# Sheet4.net
KiCad netlist of a schematic drawn in Altium Designer
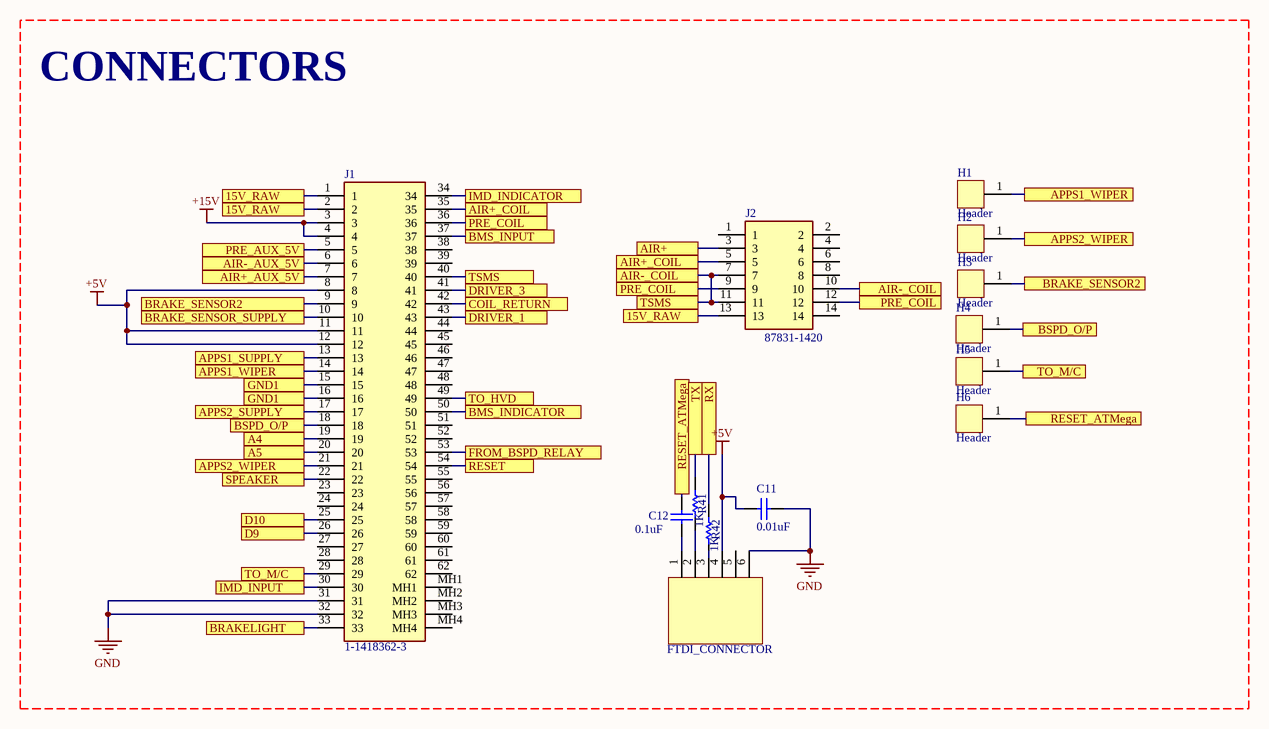
[diagram p0: Sheet4.SchDoc]

(export (version "E")
  (design (tool "Eeschema 10.0.6"))
  (components
    (comp (ref "2")
      (value "FTDI_connector")
      (footprint "FTDI")
      (libsource (lib "Schlib1") (part "FTDI_connector"))
    )
    (comp (ref "C11")
      (value "0.01uF")
      (footprint "KEMT-1206-2_N")
      (description "CAP, Ceramic, 0.1 uF, +/- 10%, 50 V, -55 to 125 degC, 1206 (3216 Metric), RoHS, Tape and Reel")
      (fields (field (name "MANUFACTURER") "Kemet"))
      (libsource (lib "Schlib1_TSAL_LV_3.1") (part "CMP-1037-04202-2"))
    )
    (comp (ref "C12")
      (value "0.1uF")
      (footprint "KEMT-1206-2_N")
      (description "CAP, Ceramic, 0.1 uF, +/- 10%, 50 V, -55 to 125 degC, 1206 (3216 Metric), RoHS, Tape and Reel")
      (fields (field (name "MANUFACTURER") "Kemet"))
      (libsource (lib "Schlib1_TSAL_LV_3.1") (part "CMP-1037-04202-2"))
    )
    (comp (ref "H1") (value "Header") (footprint "Header") (libsource (lib "Schlib1") (part "Header")))
    (comp (ref "H2") (value "Header") (footprint "Header") (libsource (lib "Schlib1") (part "Header")))
    (comp (ref "H3") (value "Header") (footprint "Header") (libsource (lib "Schlib1") (part "Header")))
    (comp (ref "H4") (value "Header") (footprint "Header") (libsource (lib "Schlib1") (part "Header")))
    (comp (ref "H5") (value "Header") (footprint "Header") (libsource (lib "Schlib1") (part "Header")))
    (comp (ref "H6") (value "Header") (footprint "Header") (libsource (lib "Schlib1") (part "Header")))
    (comp (ref "J1")
      (value "1-1418362-3")
      (footprint "SamacSys:114183623")
      (description "Connector")
      (fields (field (name "MOUSER PART NUMBER") "571-1-1418362-3"))
      (libsource (lib "*") (part "1-1418362-3"))
    )
    (comp (ref "J2")
      (value "87831-1420")
      (footprint "SamacSys:SHDR14W55P200_2X7_1665X630X640P")
      (description "Connector")
      (fields (field (name "MOUSER PART NUMBER") "538-87831-1420"))
      (libsource (lib "*") (part "87831-1420"))
    )
    (comp (ref "R41")
      (value "1K")
      (footprint "R1206")
      (fields (field (name "PART NUMBER") "CRCW120647K0FKEA") (field (name "MANUFACTURER") "Vishay Dale"))
      (libsource (lib "Schlib1") (part "RES"))
    )
    (comp (ref "R42")
      (value "1K")
      (footprint "R1206")
      (fields (field (name "PART NUMBER") "CRCW120647K0FKEA") (field (name "MANUFACTURER") "Vishay Dale"))
      (libsource (lib "Schlib1") (part "RES"))
    )
  )
  (nets
    (net (code "1") (name "+5V") (class "Default")
      (node (ref "2") (pin "4") (pinfunction "4_4") (pintype "passive"))
      (node (ref "C11") (pin "2") (pinfunction "2_2") (pintype "passive"))
      (node (ref "J1") (pin "11") (pinfunction "11_11") (pintype "passive"))
      (node (ref "J1") (pin "12") (pinfunction "12_12") (pintype "passive"))
      (node (ref "J1") (pin "8") (pinfunction "8_8") (pintype "passive"))
    )
    (net (code "2") (name "+15V") (class "Default")
      (node (ref "J1") (pin "3") (pinfunction "3_3") (pintype "passive"))
      (node (ref "J1") (pin "4") (pinfunction "4_4") (pintype "passive"))
    )
    (net (code "3") (name "/15V_RAW") (class "Default")
      (node (ref "J1") (pin "1") (pinfunction "1_1") (pintype "passive"))
      (node (ref "J1") (pin "2") (pinfunction "2_2") (pintype "passive"))
      (node (ref "J2") (pin "13") (pinfunction "13_13") (pintype "passive"))
    )
    (net (code "4") (name "/A4") (class "Default")
      (node (ref "J1") (pin "19") (pinfunction "19_19") (pintype "passive"))
    )
    (net (code "5") (name "/A5") (class "Default")
      (node (ref "J1") (pin "20") (pinfunction "20_20") (pintype "passive"))
    )
    (net (code "6") (name "/AIR+") (class "Default")
      (node (ref "J2") (pin "3") (pinfunction "3_3") (pintype "passive"))
    )
    (net (code "7") (name "/AIR+_AUX_5V") (class "Default")
      (node (ref "J1") (pin "7") (pinfunction "7_7") (pintype "passive"))
    )
    (net (code "8") (name "/AIR+_COIL") (class "Default")
      (node (ref "J1") (pin "35") (pinfunction "35_35") (pintype "passive"))
      (node (ref "J2") (pin "5") (pinfunction "5_5") (pintype "passive"))
    )
    (net (code "9") (name "/AIR-_AUX_5V") (class "Default")
      (node (ref "J1") (pin "6") (pinfunction "6_6") (pintype "passive"))
    )
    (net (code "10") (name "/AIR-_COIL") (class "Default")
      (node (ref "J1") (pin "40") (pinfunction "40_40") (pintype "passive"))
      (node (ref "J2") (pin "10") (pinfunction "10_10") (pintype "passive"))
      (node (ref "J2") (pin "11") (pinfunction "11_11") (pintype "passive"))
      (node (ref "J2") (pin "7") (pinfunction "7_7") (pintype "passive"))
    )
    (net (code "11") (name "/APPS1_SUPPLY") (class "Default")
      (node (ref "J1") (pin "13") (pinfunction "13_13") (pintype "passive"))
    )
    (net (code "12") (name "/APPS1_WIPER") (class "Default")
      (node (ref "H1") (pin "1") (pinfunction "1_1") (pintype "passive"))
      (node (ref "J1") (pin "14") (pinfunction "14_14") (pintype "passive"))
    )
    (net (code "13") (name "/APPS2_SUPPLY") (class "Default")
      (node (ref "J1") (pin "17") (pinfunction "17_17") (pintype "passive"))
    )
    (net (code "14") (name "/APPS2_WIPER") (class "Default")
      (node (ref "H2") (pin "1") (pinfunction "1_1") (pintype "passive"))
      (node (ref "J1") (pin "21") (pinfunction "21_21") (pintype "passive"))
    )
    (net (code "15") (name "/BMS_INDICATOR") (class "Default")
      (node (ref "J1") (pin "50") (pinfunction "50_50") (pintype "passive"))
    )
    (net (code "16") (name "/BMS_INPUT") (class "Default")
      (node (ref "J1") (pin "37") (pinfunction "37_37") (pintype "passive"))
    )
    (net (code "17") (name "/BRAKELIGHT") (class "Default")
      (node (ref "J1") (pin "33") (pinfunction "33_33") (pintype "passive"))
    )
    (net (code "18") (name "/BRAKE_SENSOR2") (class "Default")
      (node (ref "H3") (pin "1") (pinfunction "1_1") (pintype "passive"))
      (node (ref "J1") (pin "9") (pinfunction "9_9") (pintype "passive"))
    )
    (net (code "19") (name "/BRAKE_SENSOR_SUPPLY") (class "Default")
      (node (ref "J1") (pin "10") (pinfunction "10_10") (pintype "passive"))
    )
    (net (code "20") (name "/BSPD_O{slash}P") (class "Default")
      (node (ref "H4") (pin "1") (pinfunction "1_1") (pintype "passive"))
      (node (ref "J1") (pin "18") (pinfunction "18_18") (pintype "passive"))
    )
    (net (code "21") (name "/COIL_RETURN") (class "Default")
      (node (ref "J1") (pin "42") (pinfunction "42_42") (pintype "passive"))
    )
    (net (code "22") (name "/D9") (class "Default")
      (node (ref "J1") (pin "26") (pinfunction "26_26") (pintype "passive"))
    )
    (net (code "23") (name "/D10") (class "Default")
      (node (ref "J1") (pin "25") (pinfunction "25_25") (pintype "passive"))
    )
    (net (code "24") (name "/DRIVER_1") (class "Default")
      (node (ref "J1") (pin "43") (pinfunction "43_43") (pintype "passive"))
    )
    (net (code "25") (name "/DRIVER_3") (class "Default")
      (node (ref "J1") (pin "41") (pinfunction "41_41") (pintype "passive"))
    )
    (net (code "26") (name "/FROM_BSPD_RELAY") (class "Default")
      (node (ref "J1") (pin "53") (pinfunction "53_53") (pintype "passive"))
    )
    (net (code "27") (name "/GND1") (class "Default")
      (node (ref "J1") (pin "15") (pinfunction "15_15") (pintype "passive"))
      (node (ref "J1") (pin "16") (pinfunction "16_16") (pintype "passive"))
    )
    (net (code "28") (name "/IMD_INDICATOR") (class "Default")
      (node (ref "J1") (pin "34") (pinfunction "34_34") (pintype "passive"))
    )
    (net (code "29") (name "/IMD_INPUT") (class "Default")
      (node (ref "J1") (pin "30") (pinfunction "30_30") (pintype "passive"))
    )
    (net (code "30") (name "/PRE_AUX_5V") (class "Default")
      (node (ref "J1") (pin "5") (pinfunction "5_5") (pintype "passive"))
    )
    (net (code "31") (name "/PRE_COIL") (class "Default")
      (node (ref "J1") (pin "36") (pinfunction "36_36") (pintype "passive"))
      (node (ref "J2") (pin "12") (pinfunction "12_12") (pintype "passive"))
      (node (ref "J2") (pin "9") (pinfunction "9_9") (pintype "passive"))
    )
    (net (code "32") (name "/RESET") (class "Default")
      (node (ref "J1") (pin "54") (pinfunction "54_54") (pintype "passive"))
    )
    (net (code "33") (name "/RESET_ATMega") (class "Default")
      (node (ref "C12") (pin "2") (pinfunction "2_2") (pintype "passive"))
      (node (ref "H6") (pin "1") (pinfunction "1_1") (pintype "passive"))
    )
    (net (code "34") (name "/RX") (class "Default")
      (node (ref "R42") (pin "2") (pinfunction "2_2") (pintype "passive"))
    )
    (net (code "35") (name "/SPEAKER") (class "Default")
      (node (ref "J1") (pin "22") (pinfunction "22_22") (pintype "passive"))
    )
    (net (code "36") (name "/TO_HVD") (class "Default")
      (node (ref "J1") (pin "49") (pinfunction "49_49") (pintype "passive"))
    )
    (net (code "37") (name "/TO_M{slash}C") (class "Default")
      (node (ref "H5") (pin "1") (pinfunction "1_1") (pintype "passive"))
      (node (ref "J1") (pin "29") (pinfunction "29_29") (pintype "passive"))
    )
    (net (code "38") (name "/TX") (class "Default")
      (node (ref "R41") (pin "2") (pinfunction "2_2") (pintype "passive"))
    )
    (net (code "39") (name "GND") (class "Default")
      (node (ref "2") (pin "6") (pinfunction "6_6") (pintype "passive"))
      (node (ref "C11") (pin "1") (pinfunction "1_1") (pintype "passive"))
      (node (ref "J1") (pin "31") (pinfunction "31_31") (pintype "passive"))
      (node (ref "J1") (pin "32") (pinfunction "32_32") (pintype "passive"))
    )
    (net (code "40") (name "Net-(2-4-Pad3)") (class "Default")
      (node (ref "2") (pin "3") (pinfunction "4_3") (pintype "passive"))
      (node (ref "R42") (pin "1") (pinfunction "1_1") (pintype "passive"))
    )
    (net (code "41") (name "Net-(2-Pad1)") (class "Default")
      (node (ref "2") (pin "1") (pinfunction "1_1") (pintype "passive"))
      (node (ref "C12") (pin "1") (pinfunction "1_1") (pintype "passive"))
    )
    (net (code "42") (name "Net-(2-Pad2)") (class "Default")
      (node (ref "2") (pin "2") (pinfunction "2_2") (pintype "passive"))
      (node (ref "R41") (pin "1") (pinfunction "1_1") (pintype "passive"))
    )
    (net (code "43") (name "unconnected-(2-2-Pad5)") (class "Default")
      (node (ref "2") (pin "5") (pinfunction "2_5") (pintype "passive"))
    )
    (net (code "44") (name "unconnected-(J1-Pad23)") (class "Default")
      (node (ref "J1") (pin "23") (pinfunction "23_23") (pintype "passive"))
    )
    (net (code "45") (name "unconnected-(J1-Pad24)") (class "Default")
      (node (ref "J1") (pin "24") (pinfunction "24_24") (pintype "passive"))
    )
    (net (code "46") (name "unconnected-(J1-Pad27)") (class "Default")
      (node (ref "J1") (pin "27") (pinfunction "27_27") (pintype "passive"))
    )
    (net (code "47") (name "unconnected-(J1-Pad28)") (class "Default")
      (node (ref "J1") (pin "28") (pinfunction "28_28") (pintype "passive"))
    )
    (net (code "48") (name "unconnected-(J1-Pad38)") (class "Default")
      (node (ref "J1") (pin "38") (pinfunction "38_38") (pintype "passive"))
    )
    (net (code "49") (name "unconnected-(J1-Pad39)") (class "Default")
      (node (ref "J1") (pin "39") (pinfunction "39_39") (pintype "passive"))
    )
    (net (code "50") (name "unconnected-(J1-Pad44)") (class "Default")
      (node (ref "J1") (pin "44") (pinfunction "44_44") (pintype "passive"))
    )
    (net (code "51") (name "unconnected-(J1-Pad45)") (class "Default")
      (node (ref "J1") (pin "45") (pinfunction "45_45") (pintype "passive"))
    )
    (net (code "52") (name "unconnected-(J1-Pad46)") (class "Default")
      (node (ref "J1") (pin "46") (pinfunction "46_46") (pintype "passive"))
    )
    (net (code "53") (name "unconnected-(J1-Pad47)") (class "Default")
      (node (ref "J1") (pin "47") (pinfunction "47_47") (pintype "passive"))
    )
    (net (code "54") (name "unconnected-(J1-Pad48)") (class "Default")
      (node (ref "J1") (pin "48") (pinfunction "48_48") (pintype "passive"))
    )
    (net (code "55") (name "unconnected-(J1-Pad51)") (class "Default")
      (node (ref "J1") (pin "51") (pinfunction "51_51") (pintype "passive"))
    )
    (net (code "56") (name "unconnected-(J1-Pad52)") (class "Default")
      (node (ref "J1") (pin "52") (pinfunction "52_52") (pintype "passive"))
    )
    (net (code "57") (name "unconnected-(J1-Pad55)") (class "Default")
      (node (ref "J1") (pin "55") (pinfunction "55_55") (pintype "passive"))
    )
    (net (code "58") (name "unconnected-(J1-Pad56)") (class "Default")
      (node (ref "J1") (pin "56") (pinfunction "56_56") (pintype "passive"))
    )
    (net (code "59") (name "unconnected-(J1-Pad57)") (class "Default")
      (node (ref "J1") (pin "57") (pinfunction "57_57") (pintype "passive"))
    )
    (net (code "60") (name "unconnected-(J1-Pad58)") (class "Default")
      (node (ref "J1") (pin "58") (pinfunction "58_58") (pintype "passive"))
    )
    (net (code "61") (name "unconnected-(J1-Pad59)") (class "Default")
      (node (ref "J1") (pin "59") (pinfunction "59_59") (pintype "passive"))
    )
    (net (code "62") (name "unconnected-(J1-Pad60)") (class "Default")
      (node (ref "J1") (pin "60") (pinfunction "60_60") (pintype "passive"))
    )
    (net (code "63") (name "unconnected-(J1-Pad61)") (class "Default")
      (node (ref "J1") (pin "61") (pinfunction "61_61") (pintype "passive"))
    )
    (net (code "64") (name "unconnected-(J1-Pad62)") (class "Default")
      (node (ref "J1") (pin "62") (pinfunction "62_62") (pintype "passive"))
    )
    (net (code "65") (name "unconnected-(J1-PadMH1)") (class "Default")
      (node (ref "J1") (pin "MH1") (pinfunction "MH1_MH1") (pintype "passive"))
    )
    (net (code "66") (name "unconnected-(J1-PadMH2)") (class "Default")
      (node (ref "J1") (pin "MH2") (pinfunction "MH2_MH2") (pintype "passive"))
    )
    (net (code "67") (name "unconnected-(J1-PadMH3)") (class "Default")
      (node (ref "J1") (pin "MH3") (pinfunction "MH3_MH3") (pintype "passive"))
    )
    (net (code "68") (name "unconnected-(J1-PadMH4)") (class "Default")
      (node (ref "J1") (pin "MH4") (pinfunction "MH4_MH4") (pintype "passive"))
    )
    (net (code "69") (name "unconnected-(J2-Pad1)") (class "Default")
      (node (ref "J2") (pin "1") (pinfunction "1_1") (pintype "passive"))
    )
    (net (code "70") (name "unconnected-(J2-Pad2)") (class "Default")
      (node (ref "J2") (pin "2") (pinfunction "2_2") (pintype "passive"))
    )
    (net (code "71") (name "unconnected-(J2-Pad4)") (class "Default")
      (node (ref "J2") (pin "4") (pinfunction "4_4") (pintype "passive"))
    )
    (net (code "72") (name "unconnected-(J2-Pad6)") (class "Default")
      (node (ref "J2") (pin "6") (pinfunction "6_6") (pintype "passive"))
    )
    (net (code "73") (name "unconnected-(J2-Pad8)") (class "Default")
      (node (ref "J2") (pin "8") (pinfunction "8_8") (pintype "passive"))
    )
    (net (code "74") (name "unconnected-(J2-Pad14)") (class "Default")
      (node (ref "J2") (pin "14") (pinfunction "14_14") (pintype "passive"))
    )
  )
)
